# LED_Ring_80mm.net
KiCad netlist of a schematic drawn in Altium Designer
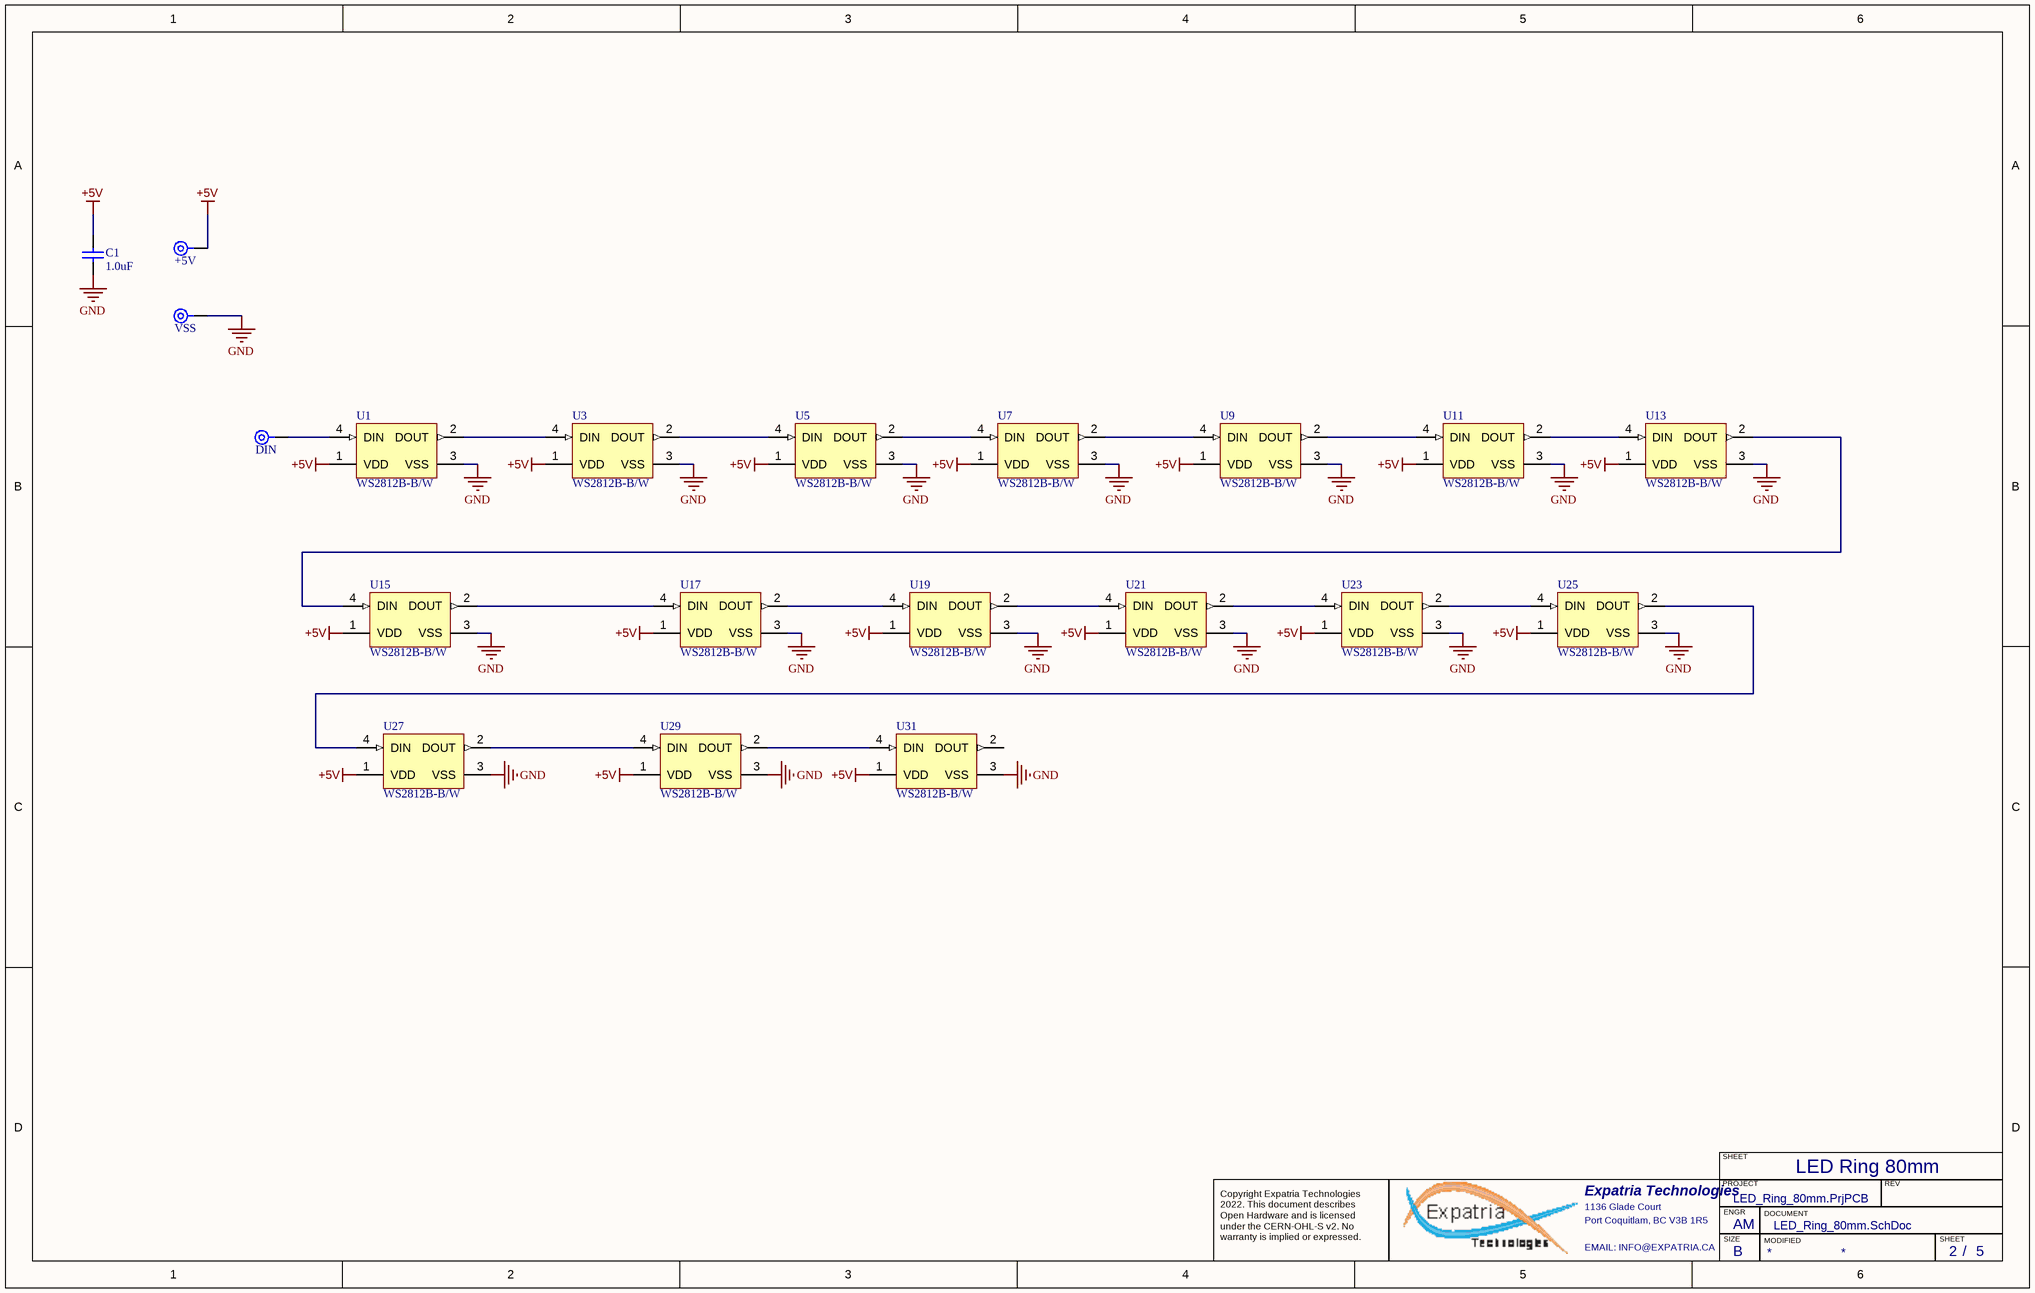
[diagram p0: LED_Ring_80mm.SchDoc]

(export (version "E")
  (design (tool "Eeschema 10.0.6"))
  (components
    (comp (ref "+5V")
      (value "Test Loop")
      (footprint "TP/LARGE")
      (description "PC TEST POINT MINIATURE")
      (libsource (lib "Universal_CNC_Breakout") (part "TL_5017"))
    )
    (comp (ref "C1")
      (value "1.0uF")
      (footprint "0402_C")
      (description "Chip capacitor")
      (fields
        (field (name "MANUFACTURER") "Samsung Electro-Mechanics")
        (field (name "PARTNUMBER") "CL05A105KA5NQNC")
      )
      (libsource (lib "Cap") (part "0402 1.0uF (105) 10% 25V"))
    )
    (comp (ref "DIN")
      (value "Test Loop")
      (footprint "TP/LARGE")
      (description "PC TEST POINT MINIATURE")
      (libsource (lib "Universal_CNC_Breakout") (part "TL_5017"))
    )
    (comp (ref "U1")
      (value "WS2812B-B/W")
      (footprint "ADA-RGB-1655_V")
      (fields (field (name "MANUFACTURER") "Worldsemi"))
      (libsource (lib "Altium Content Vault") (part "ADA-RGB-1655-4"))
    )
    (comp (ref "U3")
      (value "WS2812B-B/W")
      (footprint "ADA-RGB-1655_V")
      (fields (field (name "MANUFACTURER") "Worldsemi"))
      (libsource (lib "Altium Content Vault") (part "ADA-RGB-1655-4"))
    )
    (comp (ref "U5")
      (value "WS2812B-B/W")
      (footprint "ADA-RGB-1655_V")
      (fields (field (name "MANUFACTURER") "Worldsemi"))
      (libsource (lib "Altium Content Vault") (part "ADA-RGB-1655-4"))
    )
    (comp (ref "U7")
      (value "WS2812B-B/W")
      (footprint "ADA-RGB-1655_V")
      (fields (field (name "MANUFACTURER") "Worldsemi"))
      (libsource (lib "Altium Content Vault") (part "ADA-RGB-1655-4"))
    )
    (comp (ref "U9")
      (value "WS2812B-B/W")
      (footprint "ADA-RGB-1655_V")
      (fields (field (name "MANUFACTURER") "Worldsemi"))
      (libsource (lib "Altium Content Vault") (part "ADA-RGB-1655-4"))
    )
    (comp (ref "U11")
      (value "WS2812B-B/W")
      (footprint "ADA-RGB-1655_V")
      (fields (field (name "MANUFACTURER") "Worldsemi"))
      (libsource (lib "Altium Content Vault") (part "ADA-RGB-1655-4"))
    )
    (comp (ref "U13")
      (value "WS2812B-B/W")
      (footprint "ADA-RGB-1655_V")
      (fields (field (name "MANUFACTURER") "Worldsemi"))
      (libsource (lib "Altium Content Vault") (part "ADA-RGB-1655-4"))
    )
    (comp (ref "U15")
      (value "WS2812B-B/W")
      (footprint "ADA-RGB-1655_V")
      (fields (field (name "MANUFACTURER") "Worldsemi"))
      (libsource (lib "Altium Content Vault") (part "ADA-RGB-1655-4"))
    )
    (comp (ref "U17")
      (value "WS2812B-B/W")
      (footprint "ADA-RGB-1655_V")
      (fields (field (name "MANUFACTURER") "Worldsemi"))
      (libsource (lib "Altium Content Vault") (part "ADA-RGB-1655-4"))
    )
    (comp (ref "U19")
      (value "WS2812B-B/W")
      (footprint "ADA-RGB-1655_V")
      (fields (field (name "MANUFACTURER") "Worldsemi"))
      (libsource (lib "Altium Content Vault") (part "ADA-RGB-1655-4"))
    )
    (comp (ref "U21")
      (value "WS2812B-B/W")
      (footprint "ADA-RGB-1655_V")
      (fields (field (name "MANUFACTURER") "Worldsemi"))
      (libsource (lib "Altium Content Vault") (part "ADA-RGB-1655-4"))
    )
    (comp (ref "U23")
      (value "WS2812B-B/W")
      (footprint "ADA-RGB-1655_V")
      (fields (field (name "MANUFACTURER") "Worldsemi"))
      (libsource (lib "Altium Content Vault") (part "ADA-RGB-1655-4"))
    )
    (comp (ref "U25")
      (value "WS2812B-B/W")
      (footprint "ADA-RGB-1655_V")
      (fields (field (name "MANUFACTURER") "Worldsemi"))
      (libsource (lib "Altium Content Vault") (part "ADA-RGB-1655-4"))
    )
    (comp (ref "U27")
      (value "WS2812B-B/W")
      (footprint "ADA-RGB-1655_V")
      (fields (field (name "MANUFACTURER") "Worldsemi"))
      (libsource (lib "Altium Content Vault") (part "ADA-RGB-1655-4"))
    )
    (comp (ref "U29")
      (value "WS2812B-B/W")
      (footprint "ADA-RGB-1655_V")
      (fields (field (name "MANUFACTURER") "Worldsemi"))
      (libsource (lib "Altium Content Vault") (part "ADA-RGB-1655-4"))
    )
    (comp (ref "U31")
      (value "WS2812B-B/W")
      (footprint "ADA-RGB-1655_V")
      (fields (field (name "MANUFACTURER") "Worldsemi"))
      (libsource (lib "Altium Content Vault") (part "ADA-RGB-1655-4"))
    )
    (comp (ref "VSS")
      (value "Test Loop")
      (footprint "TP/LARGE")
      (description "PC TEST POINT MINIATURE")
      (libsource (lib "Universal_CNC_Breakout") (part "TL_5017"))
    )
  )
  (nets
    (net (code "1") (name "+5V") (class "Default")
      (node (ref "+5V") (pin "1") (pinfunction "1_1") (pintype "passive"))
      (node (ref "C1") (pin "2") (pinfunction "2_2") (pintype "passive"))
      (node (ref "U1") (pin "1") (pinfunction "VDD_1") (pintype "power_in"))
      (node (ref "U11") (pin "1") (pinfunction "VDD_1") (pintype "power_in"))
      (node (ref "U13") (pin "1") (pinfunction "VDD_1") (pintype "power_in"))
      (node (ref "U15") (pin "1") (pinfunction "VDD_1") (pintype "power_in"))
      (node (ref "U17") (pin "1") (pinfunction "VDD_1") (pintype "power_in"))
      (node (ref "U19") (pin "1") (pinfunction "VDD_1") (pintype "power_in"))
      (node (ref "U21") (pin "1") (pinfunction "VDD_1") (pintype "power_in"))
      (node (ref "U23") (pin "1") (pinfunction "VDD_1") (pintype "power_in"))
      (node (ref "U25") (pin "1") (pinfunction "VDD_1") (pintype "power_in"))
      (node (ref "U27") (pin "1") (pinfunction "VDD_1") (pintype "power_in"))
      (node (ref "U29") (pin "1") (pinfunction "VDD_1") (pintype "power_in"))
      (node (ref "U3") (pin "1") (pinfunction "VDD_1") (pintype "power_in"))
      (node (ref "U31") (pin "1") (pinfunction "VDD_1") (pintype "power_in"))
      (node (ref "U5") (pin "1") (pinfunction "VDD_1") (pintype "power_in"))
      (node (ref "U7") (pin "1") (pinfunction "VDD_1") (pintype "power_in"))
      (node (ref "U9") (pin "1") (pinfunction "VDD_1") (pintype "power_in"))
    )
    (net (code "2") (name "GND") (class "Default")
      (node (ref "C1") (pin "1") (pinfunction "1_1") (pintype "passive"))
      (node (ref "U1") (pin "3") (pinfunction "VSS_3") (pintype "power_in"))
      (node (ref "U11") (pin "3") (pinfunction "VSS_3") (pintype "power_in"))
      (node (ref "U13") (pin "3") (pinfunction "VSS_3") (pintype "power_in"))
      (node (ref "U15") (pin "3") (pinfunction "VSS_3") (pintype "power_in"))
      (node (ref "U17") (pin "3") (pinfunction "VSS_3") (pintype "power_in"))
      (node (ref "U19") (pin "3") (pinfunction "VSS_3") (pintype "power_in"))
      (node (ref "U21") (pin "3") (pinfunction "VSS_3") (pintype "power_in"))
      (node (ref "U23") (pin "3") (pinfunction "VSS_3") (pintype "power_in"))
      (node (ref "U25") (pin "3") (pinfunction "VSS_3") (pintype "power_in"))
      (node (ref "U27") (pin "3") (pinfunction "VSS_3") (pintype "power_in"))
      (node (ref "U29") (pin "3") (pinfunction "VSS_3") (pintype "power_in"))
      (node (ref "U3") (pin "3") (pinfunction "VSS_3") (pintype "power_in"))
      (node (ref "U31") (pin "3") (pinfunction "VSS_3") (pintype "power_in"))
      (node (ref "U5") (pin "3") (pinfunction "VSS_3") (pintype "power_in"))
      (node (ref "U7") (pin "3") (pinfunction "VSS_3") (pintype "power_in"))
      (node (ref "U9") (pin "3") (pinfunction "VSS_3") (pintype "power_in"))
      (node (ref "VSS") (pin "1") (pinfunction "1_1") (pintype "passive"))
    )
    (net (code "3") (name "Net-(U1-DIN)") (class "Default")
      (node (ref "DIN") (pin "1") (pinfunction "1_1") (pintype "passive"))
      (node (ref "U1") (pin "4") (pinfunction "DIN_4") (pintype "input"))
    )
    (net (code "4") (name "Net-(U1-DOUT)") (class "Default")
      (node (ref "U1") (pin "2") (pinfunction "DOUT_2") (pintype "output"))
      (node (ref "U3") (pin "4") (pinfunction "DIN_4") (pintype "input"))
    )
    (net (code "5") (name "Net-(U3-DOUT)") (class "Default")
      (node (ref "U3") (pin "2") (pinfunction "DOUT_2") (pintype "output"))
      (node (ref "U5") (pin "4") (pinfunction "DIN_4") (pintype "input"))
    )
    (net (code "6") (name "Net-(U5-DOUT)") (class "Default")
      (node (ref "U5") (pin "2") (pinfunction "DOUT_2") (pintype "output"))
      (node (ref "U7") (pin "4") (pinfunction "DIN_4") (pintype "input"))
    )
    (net (code "7") (name "Net-(U7-DOUT)") (class "Default")
      (node (ref "U7") (pin "2") (pinfunction "DOUT_2") (pintype "output"))
      (node (ref "U9") (pin "4") (pinfunction "DIN_4") (pintype "input"))
    )
    (net (code "8") (name "Net-(U11-DIN)") (class "Default")
      (node (ref "U11") (pin "4") (pinfunction "DIN_4") (pintype "input"))
      (node (ref "U9") (pin "2") (pinfunction "DOUT_2") (pintype "output"))
    )
    (net (code "9") (name "Net-(U11-DOUT)") (class "Default")
      (node (ref "U11") (pin "2") (pinfunction "DOUT_2") (pintype "output"))
      (node (ref "U13") (pin "4") (pinfunction "DIN_4") (pintype "input"))
    )
    (net (code "10") (name "Net-(U13-DOUT)") (class "Default")
      (node (ref "U13") (pin "2") (pinfunction "DOUT_2") (pintype "output"))
      (node (ref "U15") (pin "4") (pinfunction "DIN_4") (pintype "input"))
    )
    (net (code "11") (name "Net-(U15-DOUT)") (class "Default")
      (node (ref "U15") (pin "2") (pinfunction "DOUT_2") (pintype "output"))
      (node (ref "U17") (pin "4") (pinfunction "DIN_4") (pintype "input"))
    )
    (net (code "12") (name "Net-(U17-DOUT)") (class "Default")
      (node (ref "U17") (pin "2") (pinfunction "DOUT_2") (pintype "output"))
      (node (ref "U19") (pin "4") (pinfunction "DIN_4") (pintype "input"))
    )
    (net (code "13") (name "Net-(U19-DOUT)") (class "Default")
      (node (ref "U19") (pin "2") (pinfunction "DOUT_2") (pintype "output"))
      (node (ref "U21") (pin "4") (pinfunction "DIN_4") (pintype "input"))
    )
    (net (code "14") (name "Net-(U21-DOUT)") (class "Default")
      (node (ref "U21") (pin "2") (pinfunction "DOUT_2") (pintype "output"))
      (node (ref "U23") (pin "4") (pinfunction "DIN_4") (pintype "input"))
    )
    (net (code "15") (name "Net-(U23-DOUT)") (class "Default")
      (node (ref "U23") (pin "2") (pinfunction "DOUT_2") (pintype "output"))
      (node (ref "U25") (pin "4") (pinfunction "DIN_4") (pintype "input"))
    )
    (net (code "16") (name "Net-(U25-DOUT)") (class "Default")
      (node (ref "U25") (pin "2") (pinfunction "DOUT_2") (pintype "output"))
      (node (ref "U27") (pin "4") (pinfunction "DIN_4") (pintype "input"))
    )
    (net (code "17") (name "Net-(U27-DOUT)") (class "Default")
      (node (ref "U27") (pin "2") (pinfunction "DOUT_2") (pintype "output"))
      (node (ref "U29") (pin "4") (pinfunction "DIN_4") (pintype "input"))
    )
    (net (code "18") (name "Net-(U29-DOUT)") (class "Default")
      (node (ref "U29") (pin "2") (pinfunction "DOUT_2") (pintype "output"))
      (node (ref "U31") (pin "4") (pinfunction "DIN_4") (pintype "input"))
    )
    (net (code "19") (name "unconnected-(U31-DOUT-Pad2)") (class "Default")
      (node (ref "U31") (pin "2") (pinfunction "DOUT_2") (pintype "output"))
    )
  )
)
